# pan132x_breakout.net
KiCad netlist of a schematic drawn in EAGLE
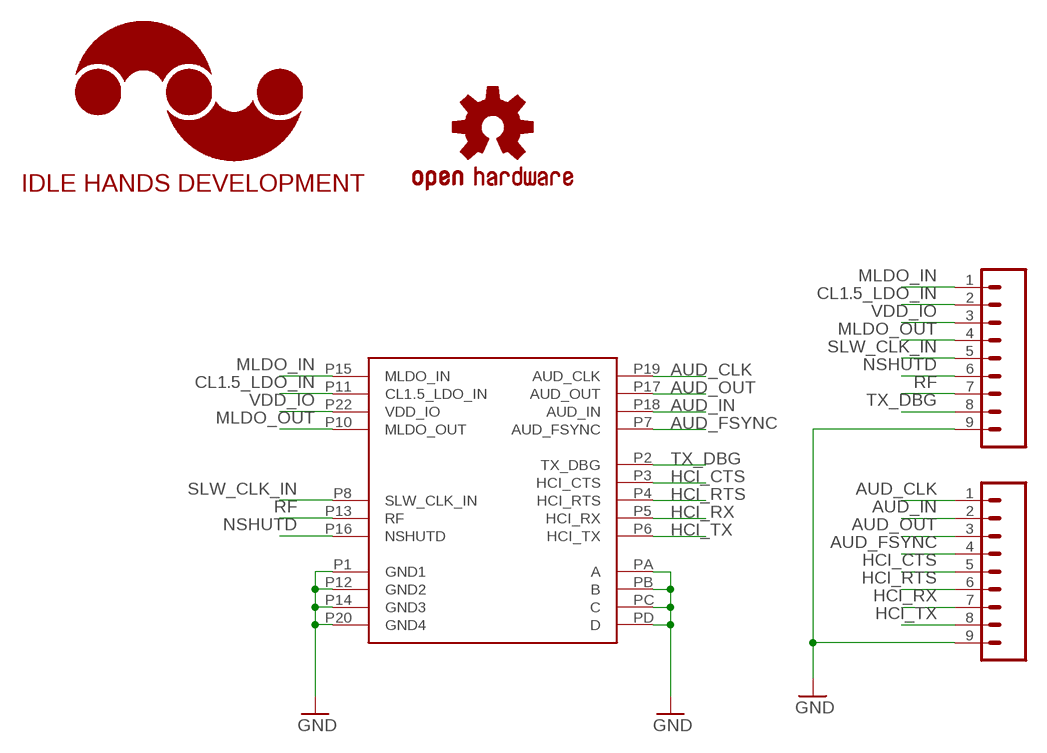
[diagram p0: schematic, sheet 1]

(export (version "E")
  (design (tool "Eeschema 10.0.6"))
  (components
    (comp (ref "JP1")
      (value "M09LOCK")
      (footprint "eagle-import:1X09_LOCK")
      (libsource (lib "eagle-import") (part "M09LOCK"))
    )
    (comp (ref "JP2")
      (value "M09LOCK")
      (footprint "eagle-import:1X09_LOCK")
      (libsource (lib "eagle-import") (part "M09LOCK"))
    )
    (comp (ref "LOGO1")
      (value "IDLEHANDS_LOGOL")
      (footprint "eagle-import:IHD-LOGO-L")
      (libsource (lib "eagle-import") (part "IDLEHANDS_LOGOL"))
    )
    (comp (ref "LOGO2")
      (value "OSHW-LOGOS")
      (footprint "eagle-import:OSHW-LOGO-S")
      (libsource (lib "eagle-import") (part "OSHW-LOGOS"))
    )
    (comp (ref "U$1")
      (value "PAN132X")
      (footprint "eagle-import:PAN13XX")
      (libsource (lib "eagle-import") (part "PAN132X"))
    )
  )
  (nets
    (net (code "1") (name "/AUD_CLK") (class "Default")
      (node (ref "JP2") (pin "1") (pinfunction "1_1") (pintype "passive"))
      (node (ref "U$1") (pin "P19") (pinfunction "AUD_CLK_P19") (pintype "bidirectional"))
    )
    (net (code "2") (name "/AUD_FSYNC") (class "Default")
      (node (ref "JP2") (pin "4") (pinfunction "4_4") (pintype "passive"))
      (node (ref "U$1") (pin "P7") (pinfunction "AUD_FSYNC_P7") (pintype "bidirectional"))
    )
    (net (code "3") (name "/AUD_IN") (class "Default")
      (node (ref "JP2") (pin "2") (pinfunction "2_2") (pintype "passive"))
      (node (ref "U$1") (pin "P18") (pinfunction "AUD_IN_P18") (pintype "bidirectional"))
    )
    (net (code "4") (name "/AUD_OUT") (class "Default")
      (node (ref "JP2") (pin "3") (pinfunction "3_3") (pintype "passive"))
      (node (ref "U$1") (pin "P17") (pinfunction "AUD_OUT_P17") (pintype "bidirectional"))
    )
    (net (code "5") (name "/CL1.5_LDO_IN") (class "Default")
      (node (ref "JP1") (pin "2") (pinfunction "2_2") (pintype "passive"))
      (node (ref "U$1") (pin "P11") (pinfunction "CL1.5_LDO_IN_P11") (pintype "power_in"))
    )
    (net (code "6") (name "/HCI_CTS") (class "Default")
      (node (ref "JP2") (pin "5") (pinfunction "5_5") (pintype "passive"))
      (node (ref "U$1") (pin "P3") (pinfunction "HCI_CTS_P3") (pintype "input"))
    )
    (net (code "7") (name "/HCI_RTS") (class "Default")
      (node (ref "JP2") (pin "6") (pinfunction "6_6") (pintype "passive"))
      (node (ref "U$1") (pin "P4") (pinfunction "HCI_RTS_P4") (pintype "output"))
    )
    (net (code "8") (name "/HCI_RX") (class "Default")
      (node (ref "JP2") (pin "7") (pinfunction "7_7") (pintype "passive"))
      (node (ref "U$1") (pin "P5") (pinfunction "HCI_RX_P5") (pintype "input"))
    )
    (net (code "9") (name "/HCI_TX") (class "Default")
      (node (ref "JP2") (pin "8") (pinfunction "8_8") (pintype "passive"))
      (node (ref "U$1") (pin "P6") (pinfunction "HCI_TX_P6") (pintype "output"))
    )
    (net (code "10") (name "/MLDO_IN") (class "Default")
      (node (ref "JP1") (pin "1") (pinfunction "1_1") (pintype "passive"))
      (node (ref "U$1") (pin "P15") (pinfunction "MLDO_IN_P15") (pintype "power_in"))
    )
    (net (code "11") (name "/MLDO_OUT") (class "Default")
      (node (ref "JP1") (pin "4") (pinfunction "4_4") (pintype "passive"))
      (node (ref "U$1") (pin "P10") (pinfunction "MLDO_OUT_P10") (pintype "power_in"))
    )
    (net (code "12") (name "/NSHUTD") (class "Default")
      (node (ref "JP1") (pin "6") (pinfunction "6_6") (pintype "passive"))
      (node (ref "U$1") (pin "P16") (pinfunction "NSHUTD_P16") (pintype "input"))
    )
    (net (code "13") (name "/RF") (class "Default")
      (node (ref "JP1") (pin "7") (pinfunction "7_7") (pintype "passive"))
      (node (ref "U$1") (pin "P13") (pinfunction "RF_P13") (pintype "bidirectional"))
    )
    (net (code "14") (name "/SLW_CLK_IN") (class "Default")
      (node (ref "JP1") (pin "5") (pinfunction "5_5") (pintype "passive"))
      (node (ref "U$1") (pin "P8") (pinfunction "SLW_CLK_IN_P8") (pintype "input"))
    )
    (net (code "15") (name "/TX_DBG") (class "Default")
      (node (ref "JP1") (pin "8") (pinfunction "8_8") (pintype "passive"))
      (node (ref "U$1") (pin "P2") (pinfunction "TX_DBG_P2") (pintype "output"))
    )
    (net (code "16") (name "/VDD_IO") (class "Default")
      (node (ref "JP1") (pin "3") (pinfunction "3_3") (pintype "passive"))
      (node (ref "U$1") (pin "P22") (pinfunction "VDD_IO_P22") (pintype "power_in"))
    )
    (net (code "17") (name "GND") (class "Default")
      (node (ref "JP1") (pin "9") (pinfunction "9_9") (pintype "passive"))
      (node (ref "JP2") (pin "9") (pinfunction "9_9") (pintype "passive"))
      (node (ref "U$1") (pin "P1") (pinfunction "GND1_P1") (pintype "bidirectional"))
      (node (ref "U$1") (pin "P12") (pinfunction "GND2_P12") (pintype "bidirectional"))
      (node (ref "U$1") (pin "P14") (pinfunction "GND3_P14") (pintype "bidirectional"))
      (node (ref "U$1") (pin "P20") (pinfunction "GND4_P20") (pintype "bidirectional"))
      (node (ref "U$1") (pin "PA") (pinfunction "A_PA") (pintype "bidirectional"))
      (node (ref "U$1") (pin "PB") (pinfunction "B_PB") (pintype "bidirectional"))
      (node (ref "U$1") (pin "PC") (pinfunction "C_PC") (pintype "bidirectional"))
      (node (ref "U$1") (pin "PD") (pinfunction "D_PD") (pintype "bidirectional"))
    )
  )
)
